# HS100R.net
KiCad netlist of a schematic drawn in EAGLE
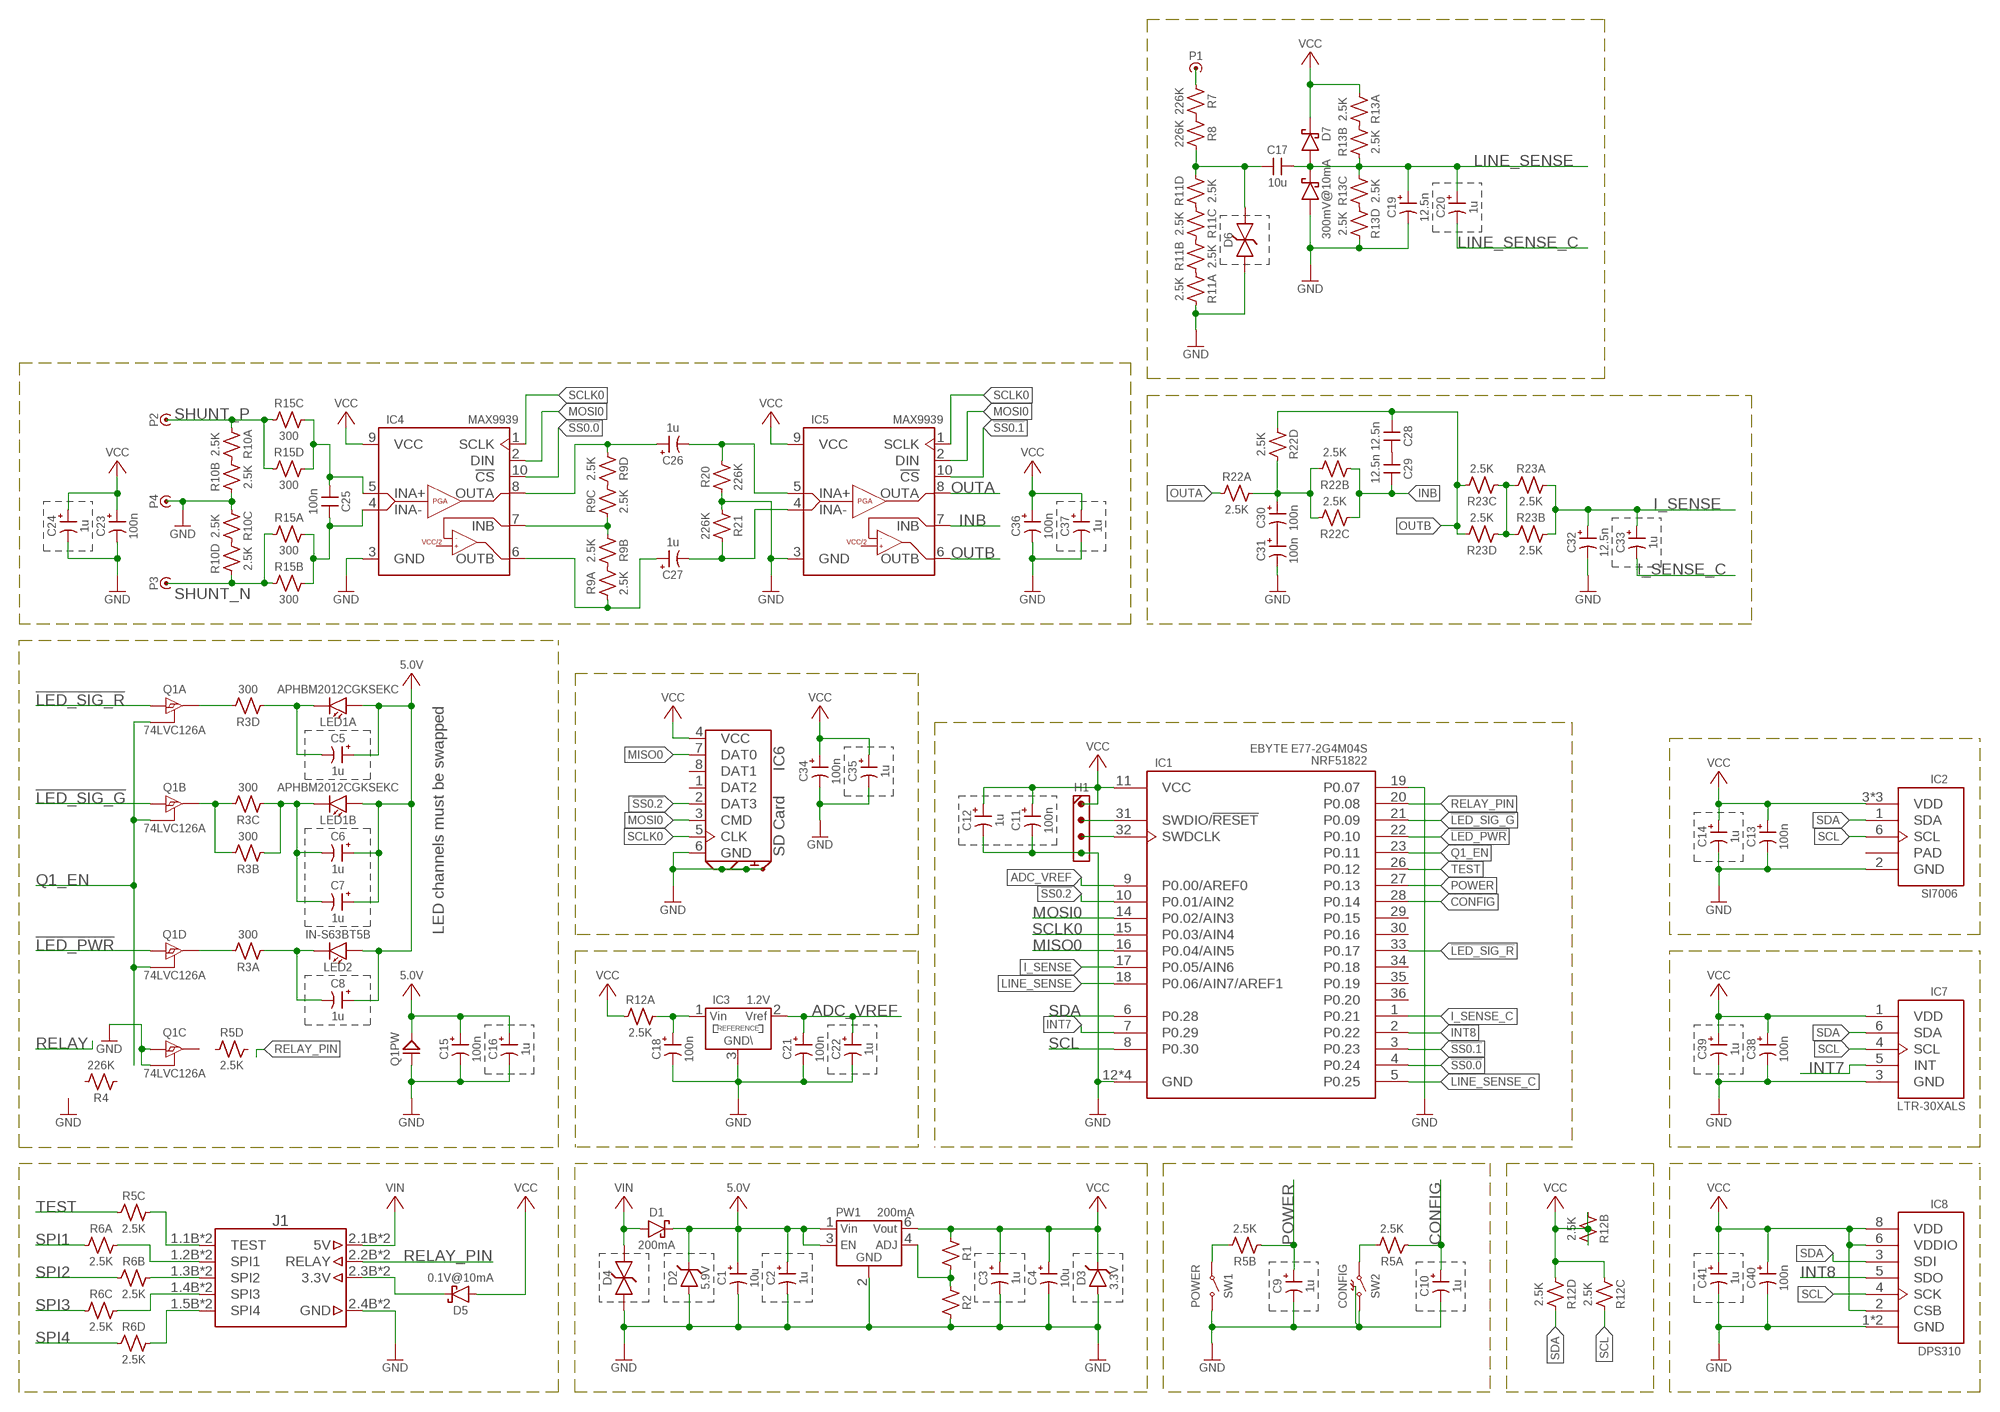
[diagram p0: schematic, sheet 1]

(export (version "E")
  (design (tool "Eeschema 10.0.6"))
  (components
    (comp (ref "C1")
      (value "10u")
      (footprint "eagle-import:1206")
      (libsource (lib "eagle-import") (part "CAPACITOR-POL-1206"))
    )
    (comp (ref "C2")
      (value "1u")
      (footprint "eagle-import:0805")
      (libsource (lib "eagle-import") (part "CAPACITOR-POL-0805"))
    )
    (comp (ref "C3")
      (value "1u")
      (footprint "eagle-import:0805")
      (libsource (lib "eagle-import") (part "CAPACITOR-POL-0805"))
    )
    (comp (ref "C4")
      (value "10u")
      (footprint "eagle-import:1206")
      (libsource (lib "eagle-import") (part "CAPACITOR-POL-1206"))
    )
    (comp (ref "C5")
      (value "1u")
      (footprint "eagle-import:0805")
      (libsource (lib "eagle-import") (part "CAPACITOR-POL-0805"))
    )
    (comp (ref "C6")
      (value "1u")
      (footprint "eagle-import:0805")
      (libsource (lib "eagle-import") (part "CAPACITOR-POL-0805"))
    )
    (comp (ref "C7")
      (value "1u")
      (footprint "eagle-import:0805")
      (libsource (lib "eagle-import") (part "CAPACITOR-POL-0805"))
    )
    (comp (ref "C8")
      (value "1u")
      (footprint "eagle-import:0805")
      (libsource (lib "eagle-import") (part "CAPACITOR-POL-0805"))
    )
    (comp (ref "C9")
      (value "1u")
      (footprint "eagle-import:0805")
      (libsource (lib "eagle-import") (part "CAPACITOR-POL-0805"))
    )
    (comp (ref "C10")
      (value "1u")
      (footprint "eagle-import:0805")
      (libsource (lib "eagle-import") (part "CAPACITOR-POL-0805"))
    )
    (comp (ref "C11")
      (value "100n")
      (footprint "eagle-import:0603")
      (libsource (lib "eagle-import") (part "CAPACITOR-POL-0603"))
    )
    (comp (ref "C12")
      (value "1u")
      (footprint "eagle-import:0805")
      (libsource (lib "eagle-import") (part "CAPACITOR-POL-0805"))
    )
    (comp (ref "C13")
      (value "100n")
      (footprint "eagle-import:0603")
      (libsource (lib "eagle-import") (part "CAPACITOR-POL-0603"))
    )
    (comp (ref "C14")
      (value "1u")
      (footprint "eagle-import:0805")
      (libsource (lib "eagle-import") (part "CAPACITOR-POL-0805"))
    )
    (comp (ref "C15")
      (value "100n")
      (footprint "eagle-import:0603")
      (libsource (lib "eagle-import") (part "CAPACITOR-POL-0603"))
    )
    (comp (ref "C16")
      (value "1u")
      (footprint "eagle-import:0805")
      (libsource (lib "eagle-import") (part "CAPACITOR-POL-0805"))
    )
    (comp (ref "C17")
      (value "10u")
      (footprint "eagle-import:1206")
      (libsource (lib "eagle-import") (part "CAPACITOR-1206"))
    )
    (comp (ref "C18")
      (value "100n")
      (footprint "eagle-import:0603")
      (libsource (lib "eagle-import") (part "CAPACITOR-POL-0603"))
    )
    (comp (ref "C19")
      (value "12.5n")
      (footprint "eagle-import:0603")
      (libsource (lib "eagle-import") (part "CAPACITOR-POL-0603"))
    )
    (comp (ref "C20")
      (value "1u")
      (footprint "eagle-import:0805")
      (libsource (lib "eagle-import") (part "CAPACITOR-POL-0805"))
    )
    (comp (ref "C21")
      (value "100n")
      (footprint "eagle-import:0603")
      (libsource (lib "eagle-import") (part "CAPACITOR-POL-0603"))
    )
    (comp (ref "C22")
      (value "1u")
      (footprint "eagle-import:0805")
      (libsource (lib "eagle-import") (part "CAPACITOR-POL-0805"))
    )
    (comp (ref "C23")
      (value "100n")
      (footprint "eagle-import:0603")
      (libsource (lib "eagle-import") (part "CAPACITOR-POL-0603"))
    )
    (comp (ref "C24")
      (value "1u")
      (footprint "eagle-import:0805")
      (libsource (lib "eagle-import") (part "CAPACITOR-POL-0805"))
    )
    (comp (ref "C25")
      (value "100n")
      (footprint "eagle-import:0603")
      (libsource (lib "eagle-import") (part "CAPACITOR-0603"))
    )
    (comp (ref "C26")
      (value "1u")
      (footprint "eagle-import:0805")
      (libsource (lib "eagle-import") (part "CAPACITOR-POL-0805"))
    )
    (comp (ref "C27")
      (value "1u")
      (footprint "eagle-import:0805")
      (libsource (lib "eagle-import") (part "CAPACITOR-POL-0805"))
    )
    (comp (ref "C28")
      (value "12.5n")
      (footprint "eagle-import:0603")
      (libsource (lib "eagle-import") (part "CAPACITOR-0603"))
    )
    (comp (ref "C29")
      (value "12.5n")
      (footprint "eagle-import:0603")
      (libsource (lib "eagle-import") (part "CAPACITOR-0603"))
    )
    (comp (ref "C30")
      (value "100n")
      (footprint "eagle-import:0603")
      (libsource (lib "eagle-import") (part "CAPACITOR-POL-0603"))
    )
    (comp (ref "C31")
      (value "100n")
      (footprint "eagle-import:0603")
      (libsource (lib "eagle-import") (part "CAPACITOR-POL-0603"))
    )
    (comp (ref "C32")
      (value "12.5n")
      (footprint "eagle-import:0603")
      (libsource (lib "eagle-import") (part "CAPACITOR-POL-0603"))
    )
    (comp (ref "C33")
      (value "1u")
      (footprint "eagle-import:0805")
      (libsource (lib "eagle-import") (part "CAPACITOR-POL-0805"))
    )
    (comp (ref "C34")
      (value "100n")
      (footprint "eagle-import:0603")
      (libsource (lib "eagle-import") (part "CAPACITOR-POL-0603"))
    )
    (comp (ref "C35")
      (value "1u")
      (footprint "eagle-import:0805")
      (libsource (lib "eagle-import") (part "CAPACITOR-POL-0805"))
    )
    (comp (ref "C36")
      (value "100n")
      (footprint "eagle-import:0603")
      (libsource (lib "eagle-import") (part "CAPACITOR-POL-0603"))
    )
    (comp (ref "C37")
      (value "1u")
      (footprint "eagle-import:0805")
      (libsource (lib "eagle-import") (part "CAPACITOR-POL-0805"))
    )
    (comp (ref "C38")
      (value "100n")
      (footprint "eagle-import:0603")
      (libsource (lib "eagle-import") (part "CAPACITOR-POL-0603"))
    )
    (comp (ref "C39")
      (value "1u")
      (footprint "eagle-import:0805")
      (libsource (lib "eagle-import") (part "CAPACITOR-POL-0805"))
    )
    (comp (ref "C40")
      (value "100n")
      (footprint "eagle-import:0603")
      (libsource (lib "eagle-import") (part "CAPACITOR-POL-0603"))
    )
    (comp (ref "C41")
      (value "1u")
      (footprint "eagle-import:0805")
      (libsource (lib "eagle-import") (part "CAPACITOR-POL-0805"))
    )
    (comp (ref "D1")
      (value "200mA")
      (footprint "eagle-import:SOD-323F")
      (libsource (lib "eagle-import") (part "DIODE_SCHOTTKY-SOD-323F"))
    )
    (comp (ref "D2")
      (value "5.9V")
      (footprint "eagle-import:SOD-323F")
      (libsource (lib "eagle-import") (part "DIODE_ZENER-SOD-323F"))
    )
    (comp (ref "D3")
      (value "3.3V")
      (footprint "eagle-import:SOD-323F")
      (libsource (lib "eagle-import") (part "DIODE_ZENER-SOD-323F"))
    )
    (comp (ref "D4")
      (value "DIODE_TVS_SOD-323F")
      (footprint "eagle-import:SOD-323F")
      (libsource (lib "eagle-import") (part "DIODE_TVS_SOD-323F"))
    )
    (comp (ref "D5")
      (value "0.1V@10mA")
      (footprint "eagle-import:SOD-323F")
      (libsource (lib "eagle-import") (part "DIODE_SCHOTTKY-SOD-323F"))
    )
    (comp (ref "D6")
      (value "DIODE_TVS_SOD-323F")
      (footprint "eagle-import:SOD-323F")
      (libsource (lib "eagle-import") (part "DIODE_TVS_SOD-323F"))
    )
    (comp (ref "D7")
      (value "300mV@10mA")
      (footprint "eagle-import:SOT-23")
      (libsource (lib "eagle-import") (part "DIODE_SCHOTTKY-2S_SOT-23"))
    )
    (comp (ref "H1")
      (value "HEADER_4X1-4X1")
      (footprint "eagle-import:PIN_1_4X1")
      (libsource (lib "eagle-import") (part "HEADER_4X1-4X1"))
    )
    (comp (ref "IC1")
      (value "EBYTE_E77-2G4M04S")
      (footprint "eagle-import:EBYTE_E77-2G4M04S")
      (libsource (lib "eagle-import") (part "EBYTE_E77-2G4M04S"))
    )
    (comp (ref "IC2")
      (value "SI7006-A20")
      (footprint "eagle-import:DFN-6_3.0_PAD")
      (libsource (lib "eagle-import") (part "SI7006-A20"))
    )
    (comp (ref "IC3")
      (value "1.2V")
      (footprint "eagle-import:SOT-23")
      (libsource (lib "eagle-import") (part "VREF_SOT-23"))
    )
    (comp (ref "IC4")
      (value "MAX9939_UMAX-10")
      (footprint "eagle-import:UMAX-10")
      (libsource (lib "eagle-import") (part "MAX9939_UMAX-10"))
    )
    (comp (ref "IC5")
      (value "MAX9939_UMAX-10")
      (footprint "eagle-import:UMAX-10")
      (libsource (lib "eagle-import") (part "MAX9939_UMAX-10"))
    )
    (comp (ref "IC6")
      (value "SD-CARD-MICRO-B")
      (footprint "eagle-import:SD-MICRO-SPRINGED-B")
      (libsource (lib "eagle-import") (part "SD-CARD-MICRO-B"))
    )
    (comp (ref "IC7")
      (value "LTR-30XALS")
      (footprint "eagle-import:LTR-30XALS")
      (libsource (lib "eagle-import") (part "LTR-30XALS"))
    )
    (comp (ref "IC8")
      (value "DPS310")
      (footprint "eagle-import:LGA-8_2.0X2.5_0.65")
      (libsource (lib "eagle-import") (part "DPS310"))
    )
    (comp (ref "J1")
      (value "PCB_CONNECTOR")
      (footprint "eagle-import:PCB_CONNECTOR")
      (libsource (lib "eagle-import") (part "PCB_CONNECTOR"))
    )
    (comp (ref "LED1")
      (value "APHBM2012CGKSEKC")
      (footprint "eagle-import:LED_DUAL-2.00X1.25")
      (libsource (lib "eagle-import") (part "LED-2X-2.00X1.25"))
    )
    (comp (ref "LED2")
      (value "IN-S63BT5B")
      (footprint "eagle-import:0603")
      (libsource (lib "eagle-import") (part "LED-0603"))
    )
    (comp (ref "P1")
      (value "PIN-PIN_R_0.6")
      (footprint "eagle-import:PIN_R_0.6_1X1")
      (libsource (lib "eagle-import") (part "PIN-PIN_R_0.6"))
    )
    (comp (ref "P2")
      (value "PIN-PIN_R_0.6")
      (footprint "eagle-import:PIN_R_0.6_1X1")
      (libsource (lib "eagle-import") (part "PIN-PIN_R_0.6"))
    )
    (comp (ref "P3")
      (value "PIN-PIN_R_0.6")
      (footprint "eagle-import:PIN_R_0.6_1X1")
      (libsource (lib "eagle-import") (part "PIN-PIN_R_0.6"))
    )
    (comp (ref "P4")
      (value "PIN-PIN_R_0.6")
      (footprint "eagle-import:PIN_R_0.6_1X1")
      (libsource (lib "eagle-import") (part "PIN-PIN_R_0.6"))
    )
    (comp (ref "PW1")
      (value "200mA")
      (footprint "eagle-import:SOT-23-5")
      (libsource (lib "eagle-import") (part "VREG_ADJ_EN-SOT-23-5"))
    )
    (comp (ref "Q1")
      (value "74LVC126A")
      (footprint "eagle-import:SSOP-14_4.4")
      (libsource (lib "eagle-import") (part "GATE-BUFFER-TRI-4X-SSOP-14_4.4"))
    )
    (comp (ref "R1")
      (value "RESISTOR-0603")
      (footprint "eagle-import:0603")
      (libsource (lib "eagle-import") (part "RESISTOR-0603"))
    )
    (comp (ref "R2")
      (value "RESISTOR-0603")
      (footprint "eagle-import:0603")
      (libsource (lib "eagle-import") (part "RESISTOR-0603"))
    )
    (comp (ref "R3")
      (value "300")
      (footprint "eagle-import:1206-QUAD")
      (libsource (lib "eagle-import") (part "RESISTOR-4X-1206"))
    )
    (comp (ref "R4")
      (value "226K")
      (footprint "eagle-import:1206")
      (libsource (lib "eagle-import") (part "RESISTOR-1206"))
    )
    (comp (ref "R5")
      (value "2.5K")
      (footprint "eagle-import:1206-QUAD")
      (libsource (lib "eagle-import") (part "RESISTOR-4X-1206"))
    )
    (comp (ref "R6")
      (value "2.5K")
      (footprint "eagle-import:1206-QUAD")
      (libsource (lib "eagle-import") (part "RESISTOR-4X-1206"))
    )
    (comp (ref "R7")
      (value "226K")
      (footprint "eagle-import:1206")
      (libsource (lib "eagle-import") (part "RESISTOR-1206"))
    )
    (comp (ref "R8")
      (value "226K")
      (footprint "eagle-import:1206")
      (libsource (lib "eagle-import") (part "RESISTOR-1206"))
    )
    (comp (ref "R9")
      (value "2.5K")
      (footprint "eagle-import:1206-QUAD")
      (libsource (lib "eagle-import") (part "RESISTOR-4X-1206"))
    )
    (comp (ref "R10")
      (value "2.5K")
      (footprint "eagle-import:1206-QUAD")
      (libsource (lib "eagle-import") (part "RESISTOR-4X-1206"))
    )
    (comp (ref "R11")
      (value "2.5K")
      (footprint "eagle-import:1206-QUAD")
      (libsource (lib "eagle-import") (part "RESISTOR-4X-1206"))
    )
    (comp (ref "R12")
      (value "2.5K")
      (footprint "eagle-import:1206-QUAD")
      (libsource (lib "eagle-import") (part "RESISTOR-4X-1206"))
    )
    (comp (ref "R13")
      (value "2.5K")
      (footprint "eagle-import:1206-QUAD")
      (libsource (lib "eagle-import") (part "RESISTOR-4X-1206"))
    )
    (comp (ref "R15")
      (value "300")
      (footprint "eagle-import:1206-QUAD")
      (libsource (lib "eagle-import") (part "RESISTOR-4X-1206"))
    )
    (comp (ref "R20")
      (value "226K")
      (footprint "eagle-import:1206")
      (libsource (lib "eagle-import") (part "RESISTOR-1206"))
    )
    (comp (ref "R21")
      (value "226K")
      (footprint "eagle-import:1206")
      (libsource (lib "eagle-import") (part "RESISTOR-1206"))
    )
    (comp (ref "R22")
      (value "2.5K")
      (footprint "eagle-import:1206-QUAD")
      (libsource (lib "eagle-import") (part "RESISTOR-4X-1206"))
    )
    (comp (ref "R23")
      (value "2.5K")
      (footprint "eagle-import:1206-QUAD")
      (libsource (lib "eagle-import") (part "RESISTOR-4X-1206"))
    )
    (comp (ref "SW1")
      (value "POWER")
      (footprint "eagle-import:GULLWING-4_4.2X3.2")
      (libsource (lib "eagle-import") (part "SWITCH-GULLWING-4_4.2X3.2"))
    )
    (comp (ref "SW2")
      (value "CONFIG")
      (footprint "eagle-import:SWITCH-RA_4.5X4.5")
      (libsource (lib "eagle-import") (part "SWITCH_SHIELD-RA_4.5X4.5"))
    )
  )
  (nets
    (net (code "2") (name "/SHUNT_N") (class "Default")
      (node (ref "P3") (pin "1.1") (pinfunction "1_1.1") (pintype "bidirectional"))
      (node (ref "R10") (pin "4") (pinfunction "1_4") (pintype "passive"))
      (node (ref "R15") (pin "1") (pinfunction "1_1") (pintype "passive"))
      (node (ref "R15") (pin "2") (pinfunction "1_2") (pintype "passive"))
    )
    (net (code "3") (name "/SHUNT_P") (class "Default")
      (node (ref "P2") (pin "1.1") (pinfunction "1_1.1") (pintype "bidirectional"))
      (node (ref "R10") (pin "1") (pinfunction "1_1") (pintype "passive"))
      (node (ref "R15") (pin "3") (pinfunction "1_3") (pintype "passive"))
      (node (ref "R15") (pin "4") (pinfunction "1_4") (pintype "passive"))
    )
    (net (code "4") (name "/SPI1") (class "Default")
      (node (ref "R6") (pin "1") (pinfunction "1_1") (pintype "passive"))
    )
    (net (code "5") (name "/SPI2") (class "Default")
      (node (ref "R6") (pin "2") (pinfunction "1_2") (pintype "passive"))
    )
    (net (code "6") (name "/SPI3") (class "Default")
      (node (ref "R6") (pin "3") (pinfunction "1_3") (pintype "passive"))
    )
    (net (code "7") (name "/SPI4") (class "Default")
      (node (ref "R6") (pin "4") (pinfunction "1_4") (pintype "passive"))
    )
    (net (code "8") (name "/~{LED_PWR}") (class "Default")
      (node (ref "IC1") (pin "22") (pinfunction "P0.10_22") (pintype "bidirectional"))
      (node (ref "Q1") (pin "12") (pinfunction "IN_12") (pintype "input"))
    )
    (net (code "9") (name "/~{LED_SIG_G}") (class "Default")
      (node (ref "IC1") (pin "21") (pinfunction "P0.09_21") (pintype "bidirectional"))
      (node (ref "Q1") (pin "5") (pinfunction "IN_5") (pintype "input"))
    )
    (net (code "10") (name "/~{LED_SIG_R}") (class "Default")
      (node (ref "IC1") (pin "33") (pinfunction "P0.17_33") (pintype "bidirectional"))
      (node (ref "Q1") (pin "2") (pinfunction "IN_2") (pintype "input"))
    )
    (net (code "11") (name "/~{SS0.0}") (class "Default")
      (node (ref "IC1") (pin "4") (pinfunction "P0.24_4") (pintype "bidirectional"))
      (node (ref "IC4") (pin "10") (pinfunction "~{CS}_10") (pintype "input"))
    )
    (net (code "12") (name "/~{SS0.1}") (class "Default")
      (node (ref "IC1") (pin "3") (pinfunction "P0.23_3") (pintype "bidirectional"))
      (node (ref "IC5") (pin "10") (pinfunction "~{CS}_10") (pintype "input"))
    )
    (net (code "13") (name "/~{SS0.2}") (class "Default")
      (node (ref "IC1") (pin "10") (pinfunction "P0.01/AIN2_10") (pintype "bidirectional"))
      (node (ref "IC6") (pin "2") (pinfunction "DAT3_2") (pintype "bidirectional"))
    )
    (net (code "14") (name "ADC_VREF") (class "Default")
      (node (ref "C21") (pin "C") (pinfunction "P_C") (pintype "passive"))
      (node (ref "C22") (pin "C") (pinfunction "P_C") (pintype "passive"))
      (node (ref "IC1") (pin "9") (pinfunction "P0.00/AREF0_9") (pintype "bidirectional"))
      (node (ref "IC3") (pin "2") (pinfunction "VOUT_2") (pintype "output"))
    )
    (net (code "15") (name "CONFIG") (class "Default")
      (node (ref "C10") (pin "C") (pinfunction "P_C") (pintype "passive"))
      (node (ref "IC1") (pin "28") (pinfunction "P0.14_28") (pintype "bidirectional"))
      (node (ref "R5") (pin "1") (pinfunction "1_1") (pintype "passive"))
    )
    (net (code "16") (name "GND") (class "Default")
      (node (ref "C1") (pin "A") (pinfunction "N_A") (pintype "passive"))
      (node (ref "C10") (pin "A") (pinfunction "N_A") (pintype "passive"))
      (node (ref "C11") (pin "A") (pinfunction "N_A") (pintype "passive"))
      (node (ref "C12") (pin "A") (pinfunction "N_A") (pintype "passive"))
      (node (ref "C13") (pin "A") (pinfunction "N_A") (pintype "passive"))
      (node (ref "C14") (pin "A") (pinfunction "N_A") (pintype "passive"))
      (node (ref "C15") (pin "A") (pinfunction "N_A") (pintype "passive"))
      (node (ref "C16") (pin "A") (pinfunction "N_A") (pintype "passive"))
      (node (ref "C18") (pin "A") (pinfunction "N_A") (pintype "passive"))
      (node (ref "C19") (pin "A") (pinfunction "N_A") (pintype "passive"))
      (node (ref "C2") (pin "A") (pinfunction "N_A") (pintype "passive"))
      (node (ref "C21") (pin "A") (pinfunction "N_A") (pintype "passive"))
      (node (ref "C22") (pin "A") (pinfunction "N_A") (pintype "passive"))
      (node (ref "C23") (pin "A") (pinfunction "N_A") (pintype "passive"))
      (node (ref "C24") (pin "A") (pinfunction "N_A") (pintype "passive"))
      (node (ref "C3") (pin "A") (pinfunction "N_A") (pintype "passive"))
      (node (ref "C31") (pin "A") (pinfunction "N_A") (pintype "passive"))
      (node (ref "C32") (pin "A") (pinfunction "N_A") (pintype "passive"))
      (node (ref "C34") (pin "A") (pinfunction "N_A") (pintype "passive"))
      (node (ref "C35") (pin "A") (pinfunction "N_A") (pintype "passive"))
      (node (ref "C36") (pin "A") (pinfunction "N_A") (pintype "passive"))
      (node (ref "C37") (pin "A") (pinfunction "N_A") (pintype "passive"))
      (node (ref "C38") (pin "A") (pinfunction "N_A") (pintype "passive"))
      (node (ref "C39") (pin "A") (pinfunction "N_A") (pintype "passive"))
      (node (ref "C4") (pin "A") (pinfunction "N_A") (pintype "passive"))
      (node (ref "C40") (pin "A") (pinfunction "N_A") (pintype "passive"))
      (node (ref "C41") (pin "A") (pinfunction "N_A") (pintype "passive"))
      (node (ref "C9") (pin "A") (pinfunction "N_A") (pintype "passive"))
      (node (ref "D2") (pin "A") (pinfunction "A_A") (pintype "passive"))
      (node (ref "D3") (pin "A") (pinfunction "A_A") (pintype "passive"))
      (node (ref "D4") (pin "A") (pinfunction "1_A") (pintype "passive"))
      (node (ref "D6") (pin "A") (pinfunction "1_A") (pintype "passive"))
      (node (ref "D7") (pin "1") (pinfunction "A_1") (pintype "passive"))
      (node (ref "H1") (pin "1.4") (pinfunction "1.4_1.4") (pintype "passive"))
      (node (ref "IC1") (pin "12") (pinfunction "GND_12") (pintype "power_in"))
      (node (ref "IC1") (pin "13") (pinfunction "GND_13") (pintype "power_in"))
      (node (ref "IC1") (pin "19") (pinfunction "P0.07_19") (pintype "bidirectional"))
      (node (ref "IC1") (pin "24") (pinfunction "GND_24") (pintype "power_in"))
      (node (ref "IC1") (pin "25") (pinfunction "GND_25") (pintype "power_in"))
      (node (ref "IC2") (pin "2") (pinfunction "GND_2") (pintype "power_in"))
      (node (ref "IC3") (pin "3") (pinfunction "GND_3") (pintype "passive"))
      (node (ref "IC4") (pin "3") (pinfunction "GND_3") (pintype "passive"))
      (node (ref "IC5") (pin "3") (pinfunction "GND_3") (pintype "passive"))
      (node (ref "IC6") (pin "6") (pinfunction "GND_6") (pintype "power_in"))
      (node (ref "IC6") (pin "DETECT") (pinfunction "DETECT1_DETECT") (pintype "passive"))
      (node (ref "IC6") (pin "SHIELD1") (pinfunction "SHIELD_SHIELD1") (pintype "passive"))
      (node (ref "IC6") (pin "SHIELD2") (pinfunction "SHIELD_SHIELD2") (pintype "passive"))
      (node (ref "IC6") (pin "SHIELD3") (pinfunction "SHIELD_SHIELD3") (pintype "passive"))
      (node (ref "IC6") (pin "SHIELD4") (pinfunction "DETECT2_SHIELD4") (pintype "passive"))
      (node (ref "IC7") (pin "3") (pinfunction "GND_3") (pintype "power_in"))
      (node (ref "IC8") (pin "1") (pinfunction "GND_1") (pintype "power_in"))
      (node (ref "IC8") (pin "7") (pinfunction "GND_7") (pintype "power_in"))
      (node (ref "J1") (pin "2.4B") (pinfunction "GND_2.4B") (pintype "passive"))
      (node (ref "J1") (pin "2.4T") (pinfunction "GND_2.4T") (pintype "passive"))
      (node (ref "P4") (pin "1.1") (pinfunction "1_1.1") (pintype "bidirectional"))
      (node (ref "PW1") (pin "2") (pinfunction "GND_2") (pintype "power_in"))
      (node (ref "Q1") (pin "10") (pinfunction "OE_10") (pintype "input"))
      (node (ref "Q1") (pin "7") (pinfunction "GND_7") (pintype "power_in"))
      (node (ref "Q1") (pin "9") (pinfunction "IN_9") (pintype "input"))
      (node (ref "R10") (pin "2") (pinfunction "1_2") (pintype "passive"))
      (node (ref "R10") (pin "3") (pinfunction "1_3") (pintype "passive"))
      (node (ref "R11") (pin "8") (pinfunction "2_8") (pintype "passive"))
      (node (ref "R13") (pin "5") (pinfunction "2_5") (pintype "passive"))
      (node (ref "R2") (pin "C") (pinfunction "2_C") (pintype "passive"))
      (node (ref "R20") (pin "A") (pinfunction "1_A") (pintype "passive"))
      (node (ref "R21") (pin "A") (pinfunction "1_A") (pintype "passive"))
      (node (ref "SW1") (pin "3") (pinfunction "2_3") (pintype "passive"))
      (node (ref "SW1") (pin "4") (pinfunction "2_4") (pintype "passive"))
      (node (ref "SW2") (pin "2") (pinfunction "2_2") (pintype "passive"))
      (node (ref "SW2") (pin "SHIELD") (pinfunction "SHIELD_SHIELD") (pintype "passive"))
    )
    (net (code "17") (name "INB") (class "Default")
      (node (ref "C29") (pin "C") (pinfunction "2_C") (pintype "passive"))
      (node (ref "IC5") (pin "7") (pinfunction "INB_7") (pintype "input"))
      (node (ref "R22") (pin "2") (pinfunction "1_2") (pintype "passive"))
      (node (ref "R22") (pin "3") (pinfunction "1_3") (pintype "passive"))
    )
    (net (code "18") (name "INT7") (class "Default")
      (node (ref "IC1") (pin "7") (pinfunction "P0.29_7") (pintype "bidirectional"))
      (node (ref "IC7") (pin "5") (pinfunction "INT_5") (pintype "open_collector"))
    )
    (net (code "19") (name "INT8") (class "Default")
      (node (ref "IC1") (pin "2") (pinfunction "P0.22_2") (pintype "bidirectional"))
      (node (ref "IC8") (pin "5") (pinfunction "SDO_5") (pintype "output"))
    )
    (net (code "20") (name "I_SENSE") (class "Default")
      (node (ref "C32") (pin "C") (pinfunction "P_C") (pintype "passive"))
      (node (ref "C33") (pin "C") (pinfunction "P_C") (pintype "passive"))
      (node (ref "IC1") (pin "17") (pinfunction "P0.05/AIN6_17") (pintype "bidirectional"))
      (node (ref "R23") (pin "7") (pinfunction "2_7") (pintype "passive"))
      (node (ref "R23") (pin "8") (pinfunction "2_8") (pintype "passive"))
    )
    (net (code "21") (name "I_SENSE_C") (class "Default")
      (node (ref "C33") (pin "A") (pinfunction "N_A") (pintype "passive"))
      (node (ref "IC1") (pin "1") (pinfunction "P0.21_1") (pintype "bidirectional"))
    )
    (net (code "22") (name "LINE_SENSE") (class "Default")
      (node (ref "C17") (pin "C") (pinfunction "2_C") (pintype "passive"))
      (node (ref "C19") (pin "C") (pinfunction "P_C") (pintype "passive"))
      (node (ref "C20") (pin "C") (pinfunction "P_C") (pintype "passive"))
      (node (ref "D7") (pin "3") (pinfunction "COMMON_3") (pintype "passive"))
      (node (ref "IC1") (pin "18") (pinfunction "P0.06/AIN7/AREF1_18") (pintype "bidirectional"))
      (node (ref "R13") (pin "2") (pinfunction "1_2") (pintype "passive"))
      (node (ref "R13") (pin "6") (pinfunction "2_6") (pintype "passive"))
    )
    (net (code "23") (name "LINE_SENSE_C") (class "Default")
      (node (ref "C20") (pin "A") (pinfunction "N_A") (pintype "passive"))
      (node (ref "IC1") (pin "5") (pinfunction "P0.25_5") (pintype "bidirectional"))
    )
    (net (code "24") (name "MISO0") (class "Default")
      (node (ref "IC1") (pin "16") (pinfunction "P0.04/AIN5_16") (pintype "bidirectional"))
      (node (ref "IC6") (pin "7") (pinfunction "DAT0_7") (pintype "bidirectional"))
    )
    (net (code "25") (name "MOSI0") (class "Default")
      (node (ref "IC1") (pin "14") (pinfunction "P0.02/AIN3_14") (pintype "bidirectional"))
      (node (ref "IC4") (pin "2") (pinfunction "DIN_2") (pintype "input"))
      (node (ref "IC5") (pin "2") (pinfunction "DIN_2") (pintype "input"))
      (node (ref "IC6") (pin "3") (pinfunction "CMD_3") (pintype "bidirectional"))
    )
    (net (code "26") (name "Net-(C5-N)") (class "Default")
      (node (ref "C5") (pin "A") (pinfunction "N_A") (pintype "passive"))
      (node (ref "LED1") (pin "K1") (pinfunction "CATHODE_K1") (pintype "passive"))
      (node (ref "R3") (pin "4") (pinfunction "1_4") (pintype "passive"))
    )
    (net (code "27") (name "Net-(C6-N)") (class "Default")
      (node (ref "C6") (pin "A") (pinfunction "N_A") (pintype "passive"))
      (node (ref "C7") (pin "A") (pinfunction "N_A") (pintype "passive"))
      (node (ref "LED1") (pin "K2") (pinfunction "CATHODE_K2") (pintype "passive"))
      (node (ref "R3") (pin "2") (pinfunction "1_2") (pintype "passive"))
      (node (ref "R3") (pin "3") (pinfunction "1_3") (pintype "passive"))
    )
    (net (code "28") (name "Net-(C8-N)") (class "Default")
      (node (ref "C8") (pin "A") (pinfunction "N_A") (pintype "passive"))
      (node (ref "LED2") (pin "C") (pinfunction "CATHODE_C") (pintype "passive"))
      (node (ref "R3") (pin "1") (pinfunction "1_1") (pintype "passive"))
    )
    (net (code "29") (name "Net-(C17-1)") (class "Default")
      (node (ref "C17") (pin "A") (pinfunction "1_A") (pintype "passive"))
      (node (ref "D6") (pin "C") (pinfunction "2_C") (pintype "passive"))
      (node (ref "R11") (pin "5") (pinfunction "2_5") (pintype "passive"))
      (node (ref "R8") (pin "C") (pinfunction "2_C") (pintype "passive"))
    )
    (net (code "30") (name "Net-(C18-P)") (class "Default")
      (node (ref "C18") (pin "C") (pinfunction "P_C") (pintype "passive"))
      (node (ref "IC3") (pin "1") (pinfunction "VIN_1") (pintype "input"))
      (node (ref "R12") (pin "8") (pinfunction "2_8") (pintype "passive"))
    )
    (net (code "31") (name "Net-(C25-1)") (class "Default")
      (node (ref "C25") (pin "A") (pinfunction "1_A") (pintype "passive"))
      (node (ref "IC4") (pin "5") (pinfunction "INA+_5") (pintype "input"))
      (node (ref "R15") (pin "5") (pinfunction "2_5") (pintype "passive"))
      (node (ref "R15") (pin "6") (pinfunction "2_6") (pintype "passive"))
    )
    (net (code "32") (name "Net-(C25-2)") (class "Default")
      (node (ref "C25") (pin "C") (pinfunction "2_C") (pintype "passive"))
      (node (ref "IC4") (pin "4") (pinfunction "INA-_4") (pintype "input"))
      (node (ref "R15") (pin "7") (pinfunction "2_7") (pintype "passive"))
      (node (ref "R15") (pin "8") (pinfunction "2_8") (pintype "passive"))
    )
    (net (code "33") (name "Net-(C26-N)") (class "Default")
      (node (ref "C26") (pin "A") (pinfunction "N_A") (pintype "passive"))
      (node (ref "IC5") (pin "5") (pinfunction "INA+_5") (pintype "input"))
      (node (ref "R20") (pin "C") (pinfunction "2_C") (pintype "passive"))
    )
    (net (code "34") (name "Net-(C26-P)") (class "Default")
      (node (ref "C26") (pin "C") (pinfunction "P_C") (pintype "passive"))
      (node (ref "IC4") (pin "8") (pinfunction "OUTA_8") (pintype "output"))
      (node (ref "R9") (pin "4") (pinfunction "1_4") (pintype "passive"))
    )
    (net (code "35") (name "Net-(C27-N)") (class "Default")
      (node (ref "C27") (pin "A") (pinfunction "N_A") (pintype "passive"))
      (node (ref "IC5") (pin "4") (pinfunction "INA-_4") (pintype "input"))
      (node (ref "R21") (pin "C") (pinfunction "2_C") (pintype "passive"))
    )
    (net (code "36") (name "Net-(C27-P)") (class "Default")
      (node (ref "C27") (pin "C") (pinfunction "P_C") (pintype "passive"))
      (node (ref "IC4") (pin "6") (pinfunction "OUTB_6") (pintype "output"))
      (node (ref "R9") (pin "1") (pinfunction "1_1") (pintype "passive"))
    )
    (net (code "37") (name "Net-(C28-2)") (class "Default")
      (node (ref "C28") (pin "C") (pinfunction "2_C") (pintype "passive"))
      (node (ref "C29") (pin "A") (pinfunction "1_A") (pintype "passive"))
    )
    (net (code "38") (name "Net-(C30-N)") (class "Default")
      (node (ref "C30") (pin "A") (pinfunction "N_A") (pintype "passive"))
      (node (ref "C31") (pin "C") (pinfunction "P_C") (pintype "passive"))
    )
    (net (code "39") (name "Net-(C30-P)") (class "Default")
      (node (ref "C30") (pin "C") (pinfunction "P_C") (pintype "passive"))
      (node (ref "R22") (pin "5") (pinfunction "2_5") (pintype "passive"))
      (node (ref "R22") (pin "6") (pinfunction "2_6") (pintype "passive"))
      (node (ref "R22") (pin "7") (pinfunction "2_7") (pintype "passive"))
      (node (ref "R22") (pin "8") (pinfunction "2_8") (pintype "passive"))
    )
    (net (code "40") (name "Net-(D5-PadC)") (class "Default")
      (node (ref "D5") (pin "C") (pinfunction "C_C") (pintype "passive"))
      (node (ref "J1") (pin "2.3B") (pinfunction "3.3V_2.3B") (pintype "passive"))
      (node (ref "J1") (pin "2.3T") (pinfunction "3.3V_2.3T") (pintype "passive"))
    )
    (net (code "41") (name "Net-(IC1-SWDCLK)") (class "Default")
      (node (ref "H1") (pin "1.3") (pinfunction "1.3_1.3") (pintype "passive"))
      (node (ref "IC1") (pin "32") (pinfunction "SWDCLK_32") (pintype "bidirectional"))
    )
    (net (code "42") (name "Net-(IC1-SWDIO{slash}~{RESET})") (class "Default")
      (node (ref "H1") (pin "1.2") (pinfunction "1.2_1.2") (pintype "passive"))
      (node (ref "IC1") (pin "31") (pinfunction "SWDIO/~{RESET}_31") (pintype "bidirectional"))
    )
    (net (code "43") (name "Net-(IC4-INB)") (class "Default")
      (node (ref "IC4") (pin "7") (pinfunction "INB_7") (pintype "input"))
      (node (ref "R9") (pin "2") (pinfunction "1_2") (pintype "passive"))
      (node (ref "R9") (pin "3") (pinfunction "1_3") (pintype "passive"))
    )
    (net (code "44") (name "Net-(P1-1)") (class "Default")
      (node (ref "P1") (pin "1.1") (pinfunction "1_1.1") (pintype "bidirectional"))
      (node (ref "R7") (pin "A") (pinfunction "1_A") (pintype "passive"))
    )
    (net (code "45") (name "Net-(PW1-ADJ)") (class "Default")
      (node (ref "PW1") (pin "4") (pinfunction "ADJ_4") (pintype "input"))
      (node (ref "R1") (pin "C") (pinfunction "2_C") (pintype "passive"))
      (node (ref "R2") (pin "A") (pinfunction "1_A") (pintype "passive"))
    )
    (net (code "46") (name "Net-(Q1A-OUT)") (class "Default")
      (node (ref "Q1") (pin "3") (pinfunction "OUT_3") (pintype "output"))
      (node (ref "R3") (pin "5") (pinfunction "2_5") (pintype "passive"))
    )
    (net (code "47") (name "Net-(Q1B-OUT)") (class "Default")
      (node (ref "Q1") (pin "6") (pinfunction "OUT_6") (pintype "output"))
      (node (ref "R3") (pin "6") (pinfunction "2_6") (pintype "passive"))
      (node (ref "R3") (pin "7") (pinfunction "2_7") (pintype "passive"))
    )
    (net (code "48") (name "Net-(Q1D-OUT)") (class "Default")
      (node (ref "Q1") (pin "11") (pinfunction "OUT_11") (pintype "output"))
      (node (ref "R3") (pin "8") (pinfunction "2_8") (pintype "passive"))
    )
    (net (code "49") (name "Net-(R5A-2)") (class "Default")
      (node (ref "R5") (pin "8") (pinfunction "2_8") (pintype "passive"))
      (node (ref "SW2") (pin "1") (pinfunction "1_1") (pintype "passive"))
    )
    (net (code "50") (name "Net-(R5B-2)") (class "Default")
      (node (ref "R5") (pin "7") (pinfunction "2_7") (pintype "passive"))
      (node (ref "SW1") (pin "1") (pinfunction "1_1") (pintype "passive"))
      (node (ref "SW1") (pin "2") (pinfunction "1_2") (pintype "passive"))
    )
    (net (code "51") (name "Net-(R5C-2)") (class "Default")
      (node (ref "J1") (pin "1.1B") (pinfunction "TEST_1.1B") (pintype "passive"))
      (node (ref "J1") (pin "1.1T") (pinfunction "TEST_1.1T") (pintype "passive"))
      (node (ref "R5") (pin "6") (pinfunction "2_6") (pintype "passive"))
    )
    (net (code "52") (name "Net-(R6A-2)") (class "Default")
      (node (ref "J1") (pin "1.2B") (pinfunction "SPI1_1.2B") (pintype "passive"))
      (node (ref "J1") (pin "1.2T") (pinfunction "SPI1_1.2T") (pintype "passive"))
      (node (ref "R6") (pin "8") (pinfunction "2_8") (pintype "passive"))
    )
    (net (code "53") (name "Net-(R6B-2)") (class "Default")
      (node (ref "J1") (pin "1.3B") (pinfunction "SPI2_1.3B") (pintype "passive"))
      (node (ref "J1") (pin "1.3T") (pinfunction "SPI2_1.3T") (pintype "passive"))
      (node (ref "R6") (pin "7") (pinfunction "2_7") (pintype "passive"))
    )
    (net (code "54") (name "Net-(R6C-2)") (class "Default")
      (node (ref "J1") (pin "1.4B") (pinfunction "SPI3_1.4B") (pintype "passive"))
      (node (ref "J1") (pin "1.4T") (pinfunction "SPI3_1.4T") (pintype "passive"))
      (node (ref "R6") (pin "6") (pinfunction "2_6") (pintype "passive"))
    )
    (net (code "55") (name "Net-(R6D-2)") (class "Default")
      (node (ref "J1") (pin "1.5B") (pinfunction "SPI4_1.5B") (pintype "passive"))
      (node (ref "J1") (pin "1.5T") (pinfunction "SPI4_1.5T") (pintype "passive"))
      (node (ref "R6") (pin "5") (pinfunction "2_5") (pintype "passive"))
    )
    (net (code "56") (name "Net-(R7-2)") (class "Default")
      (node (ref "R7") (pin "C") (pinfunction "2_C") (pintype "passive"))
      (node (ref "R8") (pin "A") (pinfunction "1_A") (pintype "passive"))
    )
    (net (code "57") (name "Net-(R9A-2)") (class "Default")
      (node (ref "R9") (pin "7") (pinfunction "2_7") (pintype "passive"))
      (node (ref "R9") (pin "8") (pinfunction "2_8") (pintype "passive"))
    )
    (net (code "58") (name "Net-(R9C-2)") (class "Default")
      (node (ref "R9") (pin "5") (pinfunction "2_5") (pintype "passive"))
      (node (ref "R9") (pin "6") (pinfunction "2_6") (pintype "passive"))
    )
    (net (code "59") (name "Net-(R10A-2)") (class "Default")
      (node (ref "R10") (pin "7") (pinfunction "2_7") (pintype "passive"))
      (node (ref "R10") (pin "8") (pinfunction "2_8") (pintype "passive"))
    )
    (net (code "60") (name "Net-(R10C-2)") (class "Default")
      (node (ref "R10") (pin "5") (pinfunction "2_5") (pintype "passive"))
      (node (ref "R10") (pin "6") (pinfunction "2_6") (pintype "passive"))
    )
    (net (code "61") (name "Net-(R11B-1)") (class "Default")
      (node (ref "R11") (pin "1") (pinfunction "1_1") (pintype "passive"))
      (node (ref "R11") (pin "2") (pinfunction "1_2") (pintype "passive"))
    )
    (net (code "62") (name "Net-(R11B-2)") (class "Default")
      (node (ref "R11") (pin "6") (pinfunction "2_6") (pintype "passive"))
      (node (ref "R11") (pin "7") (pinfunction "2_7") (pintype "passive"))
    )
    (net (code "63") (name "Net-(R11C-1)") (class "Default")
      (node (ref "R11") (pin "3") (pinfunction "1_3") (pintype "passive"))
      (node (ref "R11") (pin "4") (pinfunction "1_4") (pintype "passive"))
    )
    (net (code "64") (name "Net-(R13A-2)") (class "Default")
      (node (ref "R13") (pin "7") (pinfunction "2_7") (pintype "passive"))
      (node (ref "R13") (pin "8") (pinfunction "2_8") (pintype "passive"))
    )
    (net (code "65") (name "Net-(R13C-1)") (class "Default")
      (node (ref "R13") (pin "3") (pinfunction "1_3") (pintype "passive"))
      (node (ref "R13") (pin "4") (pinfunction "1_4") (pintype "passive"))
    )
    (net (code "66") (name "Net-(R23B-1)") (class "Default")
      (node (ref "R23") (pin "1") (pinfunction "1_1") (pintype "passive"))
      (node (ref "R23") (pin "2") (pinfunction "1_2") (pintype "passive"))
      (node (ref "R23") (pin "3") (pinfunction "1_3") (pintype "passive"))
      (node (ref "R23") (pin "4") (pinfunction "1_4") (pintype "passive"))
    )
    (net (code "67") (name "OUTA") (class "Default")
      (node (ref "IC5") (pin "8") (pinfunction "OUTA_8") (pintype "output"))
      (node (ref "R22") (pin "1") (pinfunction "1_1") (pintype "passive"))
    )
    (net (code "68") (name "OUTB") (class "Default")
      (node (ref "C28") (pin "A") (pinfunction "1_A") (pintype "passive"))
      (node (ref "IC5") (pin "6") (pinfunction "OUTB_6") (pintype "output"))
      (node (ref "R22") (pin "4") (pinfunction "1_4") (pintype "passive"))
      (node (ref "R23") (pin "5") (pinfunction "2_5") (pintype "passive"))
      (node (ref "R23") (pin "6") (pinfunction "2_6") (pintype "passive"))
    )
    (net (code "69") (name "POWER") (class "Default")
      (node (ref "C9") (pin "C") (pinfunction "P_C") (pintype "passive"))
      (node (ref "IC1") (pin "27") (pinfunction "P0.13_27") (pintype "bidirectional"))
      (node (ref "R5") (pin "2") (pinfunction "1_2") (pintype "passive"))
    )
    (net (code "70") (name "Q1_EN") (class "Default")
      (node (ref "IC1") (pin "23") (pinfunction "P0.11_23") (pintype "bidirectional"))
      (node (ref "Q1") (pin "1") (pinfunction "OE_1") (pintype "input"))
      (node (ref "Q1") (pin "13") (pinfunction "OE_13") (pintype "input"))
      (node (ref "Q1") (pin "4") (pinfunction "OE_4") (pintype "input"))
    )
    (net (code "71") (name "RELAY_PIN") (class "Default")
      (node (ref "IC1") (pin "20") (pinfunction "P0.08_20") (pintype "bidirectional"))
      (node (ref "J1") (pin "2.2B") (pinfunction "RELAY_2.2B") (pintype "input"))
      (node (ref "J1") (pin "2.2T") (pinfunction "RELAY_2.2T") (pintype "input"))
    )
    (net (code "72") (name "SCL") (class "Default")
      (node (ref "IC1") (pin "8") (pinfunction "P0.30_8") (pintype "bidirectional"))
      (node (ref "IC2") (pin "6") (pinfunction "SCL_6") (pintype "open_collector"))
      (node (ref "IC7") (pin "4") (pinfunction "SCL_4") (pintype "open_collector"))
      (node (ref "IC8") (pin "4") (pinfunction "SCK_4") (pintype "input"))
      (node (ref "R12") (pin "6") (pinfunction "2_6") (pintype "passive"))
    )
    (net (code "73") (name "SCLK0") (class "Default")
      (node (ref "IC1") (pin "15") (pinfunction "P0.03/AIN4_15") (pintype "bidirectional"))
      (node (ref "IC4") (pin "1") (pinfunction "SCLK_1") (pintype "input"))
      (node (ref "IC5") (pin "1") (pinfunction "SCLK_1") (pintype "input"))
      (node (ref "IC6") (pin "5") (pinfunction "CLK_5") (pintype "input"))
    )
    (net (code "74") (name "SDA") (class "Default")
      (node (ref "IC1") (pin "6") (pinfunction "P0.28_6") (pintype "bidirectional"))
      (node (ref "IC2") (pin "1") (pinfunction "SDA_1") (pintype "open_collector"))
      (node (ref "IC7") (pin "6") (pinfunction "SDA_6") (pintype "open_collector"))
      (node (ref "IC8") (pin "3") (pinfunction "SDI_3") (pintype "bidirectional"))
      (node (ref "R12") (pin "5") (pinfunction "2_5") (pintype "passive"))
    )
    (net (code "75") (name "TEST") (class "Default")
      (node (ref "IC1") (pin "26") (pinfunction "P0.12_26") (pintype "bidirectional"))
      (node (ref "R5") (pin "3") (pinfunction "1_3") (pintype "passive"))
    )
    (net (code "76") (name "VCC") (class "Default")
      (node (ref "C11") (pin "C") (pinfunction "P_C") (pintype "passive"))
      (node (ref "C12") (pin "C") (pinfunction "P_C") (pintype "passive"))
      (node (ref "C13") (pin "C") (pinfunction "P_C") (pintype "passive"))
      (node (ref "C14") (pin "C") (pinfunction "P_C") (pintype "passive"))
      (node (ref "C23") (pin "C") (pinfunction "P_C") (pintype "passive"))
      (node (ref "C24") (pin "C") (pinfunction "P_C") (pintype "passive"))
      (node (ref "C3") (pin "C") (pinfunction "P_C") (pintype "passive"))
      (node (ref "C34") (pin "C") (pinfunction "P_C") (pintype "passive"))
      (node (ref "C35") (pin "C") (pinfunction "P_C") (pintype "passive"))
      (node (ref "C36") (pin "C") (pinfunction "P_C") (pintype "passive"))
      (node (ref "C37") (pin "C") (pinfunction "P_C") (pintype "passive"))
      (node (ref "C38") (pin "C") (pinfunction "P_C") (pintype "passive"))
      (node (ref "C39") (pin "C") (pinfunction "P_C") (pintype "passive"))
      (node (ref "C4") (pin "C") (pinfunction "P_C") (pintype "passive"))
      (node (ref "C40") (pin "C") (pinfunction "P_C") (pintype "passive"))
      (node (ref "C41") (pin "C") (pinfunction "P_C") (pintype "passive"))
      (node (ref "D3") (pin "C") (pinfunction "C_C") (pintype "passive"))
      (node (ref "D5") (pin "A") (pinfunction "A_A") (pintype "passive"))
      (node (ref "D7") (pin "2") (pinfunction "C_2") (pintype "passive"))
      (node (ref "H1") (pin "1.1") (pinfunction "1.1_1.1") (pintype "passive"))
      (node (ref "IC1") (pin "11") (pinfunction "VCC_11") (pintype "power_in"))
      (node (ref "IC2") (pin "3") (pinfunction "VDD_3") (pintype "power_in"))
      (node (ref "IC2") (pin "4") (pinfunction "VDD_4") (pintype "power_in"))
      (node (ref "IC2") (pin "5") (pinfunction "VDD_5") (pintype "power_in"))
      (node (ref "IC4") (pin "9") (pinfunction "VCC_9") (pintype "passive"))
      (node (ref "IC5") (pin "9") (pinfunction "VCC_9") (pintype "passive"))
      (node (ref "IC6") (pin "4") (pinfunction "VCC_4") (pintype "power_in"))
      (node (ref "IC7") (pin "1") (pinfunction "VDD_1") (pintype "power_in"))
      (node (ref "IC8") (pin "2") (pinfunction "CSB_2") (pintype "passive"))
      (node (ref "IC8") (pin "6") (pinfunction "VDDIO_6") (pintype "power_in"))
      (node (ref "IC8") (pin "8") (pinfunction "VDD_8") (pintype "power_in"))
      (node (ref "PW1") (pin "6") (pinfunction "VOUT_6") (pintype "power_in"))
      (node (ref "R1") (pin "A") (pinfunction "1_A") (pintype "passive"))
      (node (ref "R12") (pin "1") (pinfunction "1_1") (pintype "passive"))
      (node (ref "R12") (pin "2") (pinfunction "1_2") (pintype "passive"))
      (node (ref "R12") (pin "3") (pinfunction "1_3") (pintype "passive"))
      (node (ref "R12") (pin "4") (pinfunction "1_4") (pintype "passive"))
      (node (ref "R12") (pin "7") (pinfunction "2_7") (pintype "passive"))
      (node (ref "R13") (pin "1") (pinfunction "1_1") (pintype "passive"))
    )
    (net (code "77") (name "VCC-5.0V") (class "Default")
      (node (ref "C1") (pin "C") (pinfunction "P_C") (pintype "passive"))
      (node (ref "C15") (pin "C") (pinfunction "P_C") (pintype "passive"))
      (node (ref "C16") (pin "C") (pinfunction "P_C") (pintype "passive"))
      (node (ref "C2") (pin "C") (pinfunction "P_C") (pintype "passive"))
      (node (ref "C5") (pin "C") (pinfunction "P_C") (pintype "passive"))
      (node (ref "C6") (pin "C") (pinfunction "P_C") (pintype "passive"))
      (node (ref "C7") (pin "C") (pinfunction "P_C") (pintype "passive"))
      (node (ref "C8") (pin "C") (pinfunction "P_C") (pintype "passive"))
      (node (ref "D1") (pin "C") (pinfunction "C_C") (pintype "passive"))
      (node (ref "D2") (pin "C") (pinfunction "C_C") (pintype "passive"))
      (node (ref "LED1") (pin "A1") (pinfunction "ANODE_A1") (pintype "passive"))
      (node (ref "LED1") (pin "A2") (pinfunction "ANODE_A2") (pintype "passive"))
      (node (ref "LED2") (pin "A") (pinfunction "ANODE_A") (pintype "passive"))
      (node (ref "PW1") (pin "1") (pinfunction "VIN_1") (pintype "power_in"))
      (node (ref "PW1") (pin "3") (pinfunction "EN_3") (pintype "input"))
      (node (ref "Q1") (pin "14") (pinfunction "VCC_14") (pintype "power_in"))
    )
    (net (code "78") (name "VIN") (class "Default")
      (node (ref "D1") (pin "A") (pinfunction "A_A") (pintype "passive"))
      (node (ref "D4") (pin "C") (pinfunction "2_C") (pintype "passive"))
      (node (ref "J1") (pin "2.1B") (pinfunction "5V_2.1B") (pintype "passive"))
      (node (ref "J1") (pin "2.1T") (pinfunction "5V_2.1T") (pintype "passive"))
    )
    (net (code "79") (name "unconnected-(IC1-P0.15-Pad29)") (class "Default")
      (node (ref "IC1") (pin "29") (pinfunction "P0.15_29") (pintype "bidirectional"))
    )
    (net (code "80") (name "unconnected-(IC1-P0.16-Pad30)") (class "Default")
      (node (ref "IC1") (pin "30") (pinfunction "P0.16_30") (pintype "bidirectional"))
    )
    (net (code "81") (name "unconnected-(IC1-P0.18-Pad34)") (class "Default")
      (node (ref "IC1") (pin "34") (pinfunction "P0.18_34") (pintype "bidirectional"))
    )
    (net (code "82") (name "unconnected-(IC1-P0.19-Pad35)") (class "Default")
      (node (ref "IC1") (pin "35") (pinfunction "P0.19_35") (pintype "bidirectional"))
    )
    (net (code "83") (name "unconnected-(IC1-P0.20-Pad36)") (class "Default")
      (node (ref "IC1") (pin "36") (pinfunction "P0.20_36") (pintype "bidirectional"))
    )
    (net (code "84") (name "unconnected-(IC2-PAD-PadCENTER)") (class "Default")
      (node (ref "IC2") (pin "CENTER") (pinfunction "PAD_CENTER") (pintype "passive"))
    )
    (net (code "85") (name "unconnected-(IC6-DAT1-Pad8)") (class "Default")
      (node (ref "IC6") (pin "8") (pinfunction "DAT1_8") (pintype "bidirectional"))
    )
    (net (code "86") (name "unconnected-(IC6-DAT2-Pad1)") (class "Default")
      (node (ref "IC6") (pin "1") (pinfunction "DAT2_1") (pintype "bidirectional"))
    )
    (net (code "87") (name "unconnected-(Q1C-OUT-Pad8)") (class "Default")
      (node (ref "Q1") (pin "8") (pinfunction "OUT_8") (pintype "output"))
    )
    (net (code "88") (name "unconnected-(R4-1-PadA)") (class "Default")
      (node (ref "R4") (pin "A") (pinfunction "1_A") (pintype "passive"))
    )
    (net (code "89") (name "unconnected-(R4-2-PadC)") (class "Default")
      (node (ref "R4") (pin "C") (pinfunction "2_C") (pintype "passive"))
    )
    (net (code "90") (name "unconnected-(R5D-1-Pad4)") (class "Default")
      (node (ref "R5") (pin "4") (pinfunction "1_4") (pintype "passive"))
    )
    (net (code "91") (name "unconnected-(R5D-2-Pad5)") (class "Default")
      (node (ref "R5") (pin "5") (pinfunction "2_5") (pintype "passive"))
    )
  )
)
